# Sheet1.net
KiCad netlist of a schematic drawn in Altium Designer
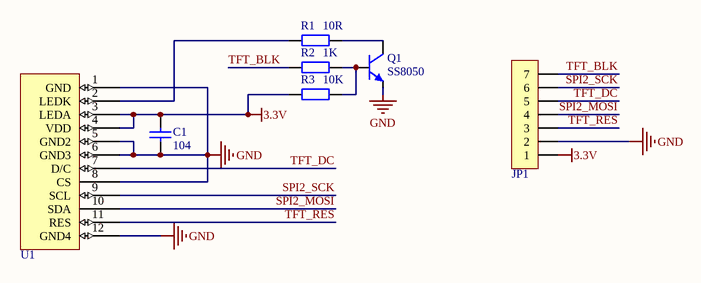
[diagram p0: Sheet1.SchDoc]

(export (version "E")
  (design (tool "Eeschema 10.0.6"))
  (components
    (comp (ref "C1")
      (value "104")
      (footprint "C 0603_L")
      (description "贴片电容")
      (libsource (lib "0.1 - 电阻-电容-电感") (part "C"))
    )
    (comp (ref "JP1")
      (value "HDR-1X7")
      (footprint "HDR2.54-M-LI-7P")
      (description "7P接插件")
      (libsource (lib "5.4 - 接插件-脚距2.54 (100mil) ") (part "Header 7"))
    )
    (comp (ref "Q1")
      (value "SS8050")
      (footprint "SOT23-3N")
      (description "高频放大-NPN型")
      (libsource (lib "0.4 - 三极管-场效应管-可控硅") (part "8050-SMD"))
    )
    (comp (ref "R1")
      (value "10R")
      (footprint "R 0603_L")
      (description "贴片电阻")
      (libsource (lib "0.1 - 电阻-电容-电感") (part "R"))
    )
    (comp (ref "R2")
      (value "1K")
      (footprint "R 0603_L")
      (description "贴片电阻")
      (libsource (lib "0.1 - 电阻-电容-电感") (part "R"))
    )
    (comp (ref "R3")
      (value "10K")
      (footprint "R 0603_L")
      (description "贴片电阻")
      (libsource (lib "0.1 - 电阻-电容-电感") (part "R"))
    )
    (comp (ref "U1") (value "TFT-1.3") (footprint "TFT-1.3") (libsource (lib "DingXuan") (part "TFT-1.3")))
  )
  (nets
    (net (code "1") (name "/SPI2_MOSI") (class "Default")
      (node (ref "JP1") (pin "4") (pinfunction "4_4") (pintype "passive"))
      (node (ref "U1") (pin "10") (pinfunction "SDA_10") (pintype "power_in"))
    )
    (net (code "2") (name "/SPI2_SCK") (class "Default")
      (node (ref "JP1") (pin "6") (pinfunction "6_6") (pintype "passive"))
      (node (ref "U1") (pin "9") (pinfunction "SCL_9") (pintype "bidirectional"))
    )
    (net (code "3") (name "/TFT_BLK") (class "Default")
      (node (ref "JP1") (pin "7") (pinfunction "7_7") (pintype "passive"))
      (node (ref "R2") (pin "1") (pinfunction "1_1") (pintype "passive"))
    )
    (net (code "4") (name "/TFT_DC") (class "Default")
      (node (ref "JP1") (pin "5") (pinfunction "5_5") (pintype "passive"))
      (node (ref "U1") (pin "7") (pinfunction "D/C_7") (pintype "bidirectional"))
    )
    (net (code "5") (name "/TFT_RES") (class "Default")
      (node (ref "JP1") (pin "3") (pinfunction "3_3") (pintype "passive"))
      (node (ref "U1") (pin "11") (pinfunction "RES_11") (pintype "bidirectional"))
    )
    (net (code "6") (name "3.3V") (class "Default")
      (node (ref "C1") (pin "1") (pinfunction "1_1") (pintype "passive"))
      (node (ref "JP1") (pin "1") (pinfunction "1_1") (pintype "passive"))
      (node (ref "R3") (pin "2") (pinfunction "2_2") (pintype "passive"))
      (node (ref "U1") (pin "3") (pinfunction "LEDA_3") (pintype "bidirectional"))
      (node (ref "U1") (pin "4") (pinfunction "VDD_4") (pintype "bidirectional"))
    )
    (net (code "7") (name "GND") (class "Default")
      (node (ref "C1") (pin "2") (pinfunction "2_2") (pintype "passive"))
      (node (ref "JP1") (pin "2") (pinfunction "2_2") (pintype "passive"))
      (node (ref "Q1") (pin "2") (pinfunction "E_2") (pintype "passive"))
      (node (ref "U1") (pin "1") (pinfunction "GND_1") (pintype "bidirectional"))
      (node (ref "U1") (pin "12") (pinfunction "GND4_12") (pintype "bidirectional"))
      (node (ref "U1") (pin "5") (pinfunction "GND2_5") (pintype "bidirectional"))
      (node (ref "U1") (pin "6") (pinfunction "GND3_6") (pintype "bidirectional"))
      (node (ref "U1") (pin "8") (pinfunction "CS_8") (pintype "power_in"))
    )
    (net (code "8") (name "Net-(Q1-B)") (class "Default")
      (node (ref "Q1") (pin "1") (pinfunction "B_1") (pintype "passive"))
      (node (ref "R2") (pin "2") (pinfunction "2_2") (pintype "passive"))
      (node (ref "R3") (pin "1") (pinfunction "1_1") (pintype "passive"))
    )
    (net (code "9") (name "Net-(Q1-C)") (class "Default")
      (node (ref "Q1") (pin "3") (pinfunction "C_3") (pintype "passive"))
      (node (ref "R1") (pin "1") (pinfunction "1_1") (pintype "passive"))
    )
    (net (code "10") (name "Net-(U1-LEDK)") (class "Default")
      (node (ref "R1") (pin "2") (pinfunction "2_2") (pintype "passive"))
      (node (ref "U1") (pin "2") (pinfunction "LEDK_2") (pintype "bidirectional"))
    )
  )
)
